# Power_Distribution_-_Spare_Load_Switch.net
KiCad netlist of a schematic drawn in Altium Designer
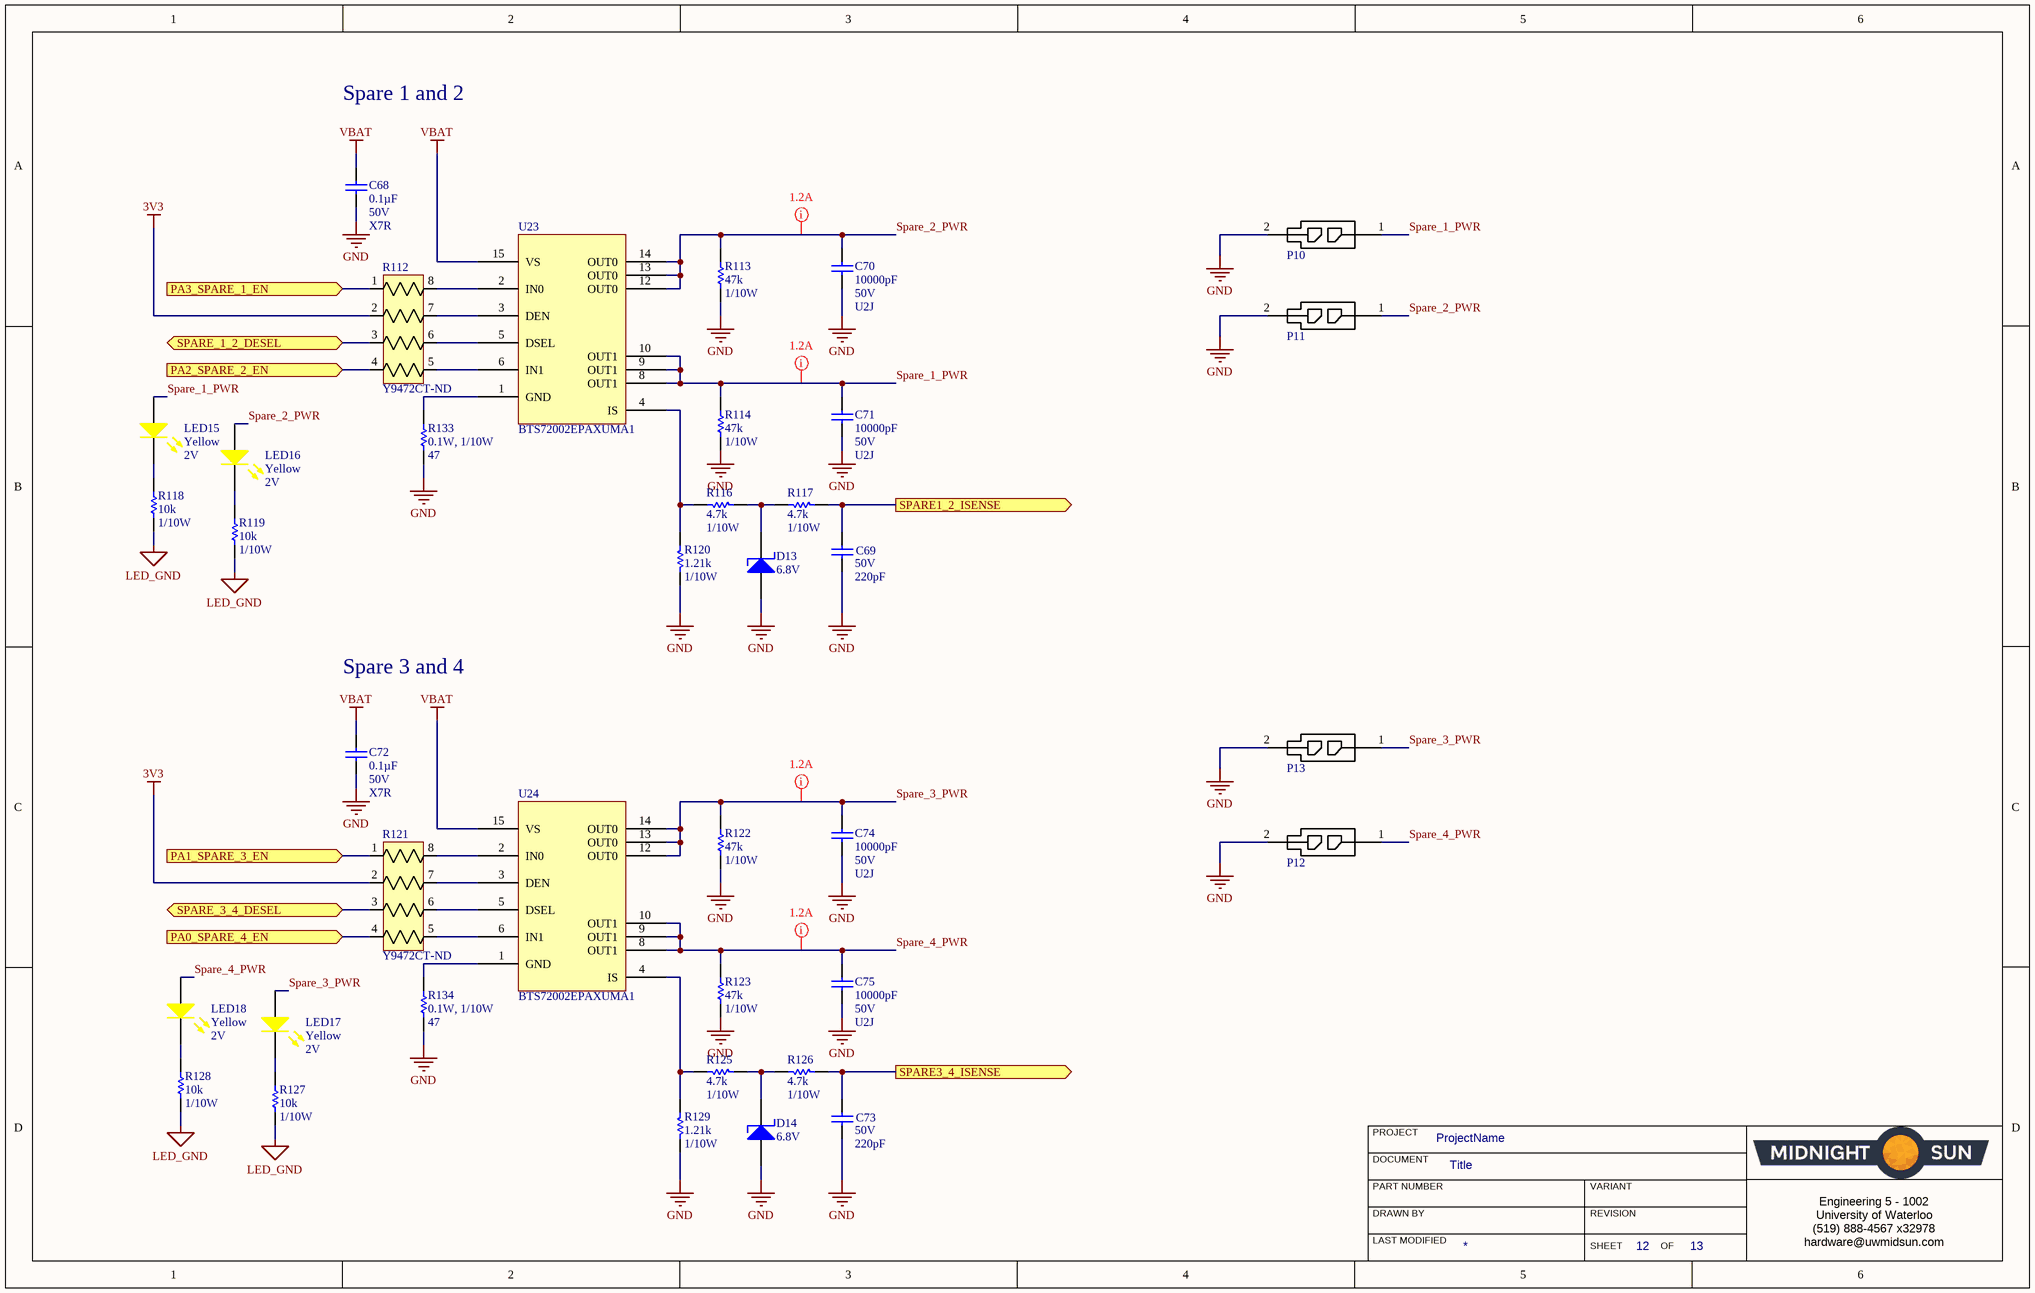
[diagram p0: Power Distribution - Spare Load Switch.SchDoc]

(export (version "E")
  (design (tool "Eeschema 10.0.6"))
  (components
    (comp (ref "C68")
      (value "CAP CER 0.1UF 50V 10% X7R 0603")
      (footprint "CAP, 0603")
      (description "0.10µF ±10% 50V Ceramic Capacitor X7R 0603 (1608 Metric)")
      (fields
        (field (name "TOLERANCE") "±10%")
        (field (name "CAPACITANCE") "0.1µF")
        (field (name "VOLTAGE") "50V")
        (field (name "TEMPERATURE COEFFICIENT") "X7R")
      )
      (libsource (lib "Schematic Diagrams") (part "CAP CER 0.1UF 50V 10% X7R 0603"))
    )
    (comp (ref "C69")
      (value "CAP CER 220PF 50V C0G/NP0 0603")
      (footprint "CAP, 0603")
      (description "220pF ±5% 50V Ceramic Capacitor C0G, NP0 0603 (1608 Metric)")
      (fields
        (field (name "MANUFACTURER") "KEMET")
        (field (name "TOLERANCE") "5%")
        (field (name "VOLTAGE RATING") "50V")
        (field (name "CAPACITANCE") "220pF")
      )
      (libsource (lib "Schematic Diagrams") (part "CAP CER 220PF 50V C0G/NP0 0603"))
    )
    (comp (ref "C70")
      (value "CAP CER 10nF 50V 5% X7R 0603")
      (footprint "CAP, 0603")
      (description "10000pF ±5% 50V Ceramic Capacitor U2J 0603 (1608 Metric)")
      (fields
        (field (name "TOLERANCE") "±5%")
        (field (name "CAPACITANCE") "10000pF")
        (field (name "VOLTAGE") "50V")
        (field (name "TEMPERATURE COEFFICIENT") "U2J")
      )
      (libsource (lib "Schematic Diagrams") (part "CAP CER 10nF 50V 5% X7R 0603"))
    )
    (comp (ref "C71")
      (value "CAP CER 10nF 50V 5% X7R 0603")
      (footprint "CAP, 0603")
      (description "10000pF ±5% 50V Ceramic Capacitor U2J 0603 (1608 Metric)")
      (fields
        (field (name "TOLERANCE") "±5%")
        (field (name "CAPACITANCE") "10000pF")
        (field (name "VOLTAGE") "50V")
        (field (name "TEMPERATURE COEFFICIENT") "U2J")
      )
      (libsource (lib "Schematic Diagrams") (part "CAP CER 10nF 50V 5% X7R 0603"))
    )
    (comp (ref "C72")
      (value "CAP CER 0.1UF 50V 10% X7R 0603")
      (footprint "CAP, 0603")
      (description "0.10µF ±10% 50V Ceramic Capacitor X7R 0603 (1608 Metric)")
      (fields
        (field (name "TOLERANCE") "±10%")
        (field (name "CAPACITANCE") "0.1µF")
        (field (name "VOLTAGE") "50V")
        (field (name "TEMPERATURE COEFFICIENT") "X7R")
      )
      (libsource (lib "Schematic Diagrams") (part "CAP CER 0.1UF 50V 10% X7R 0603"))
    )
    (comp (ref "C73")
      (value "CAP CER 220PF 50V C0G/NP0 0603")
      (footprint "CAP, 0603")
      (description "220pF ±5% 50V Ceramic Capacitor C0G, NP0 0603 (1608 Metric)")
      (fields
        (field (name "MANUFACTURER") "KEMET")
        (field (name "TOLERANCE") "5%")
        (field (name "VOLTAGE RATING") "50V")
        (field (name "CAPACITANCE") "220pF")
      )
      (libsource (lib "Schematic Diagrams") (part "CAP CER 220PF 50V C0G/NP0 0603"))
    )
    (comp (ref "C74")
      (value "CAP CER 10nF 50V 5% X7R 0603")
      (footprint "CAP, 0603")
      (description "10000pF ±5% 50V Ceramic Capacitor U2J 0603 (1608 Metric)")
      (fields
        (field (name "TOLERANCE") "±5%")
        (field (name "CAPACITANCE") "10000pF")
        (field (name "VOLTAGE") "50V")
        (field (name "TEMPERATURE COEFFICIENT") "U2J")
      )
      (libsource (lib "Schematic Diagrams") (part "CAP CER 10nF 50V 5% X7R 0603"))
    )
    (comp (ref "C75")
      (value "CAP CER 10nF 50V 5% X7R 0603")
      (footprint "CAP, 0603")
      (description "10000pF ±5% 50V Ceramic Capacitor U2J 0603 (1608 Metric)")
      (fields
        (field (name "TOLERANCE") "±5%")
        (field (name "CAPACITANCE") "10000pF")
        (field (name "VOLTAGE") "50V")
        (field (name "TEMPERATURE COEFFICIENT") "U2J")
      )
      (libsource (lib "Schematic Diagrams") (part "CAP CER 10nF 50V 5% X7R 0603"))
    )
    (comp (ref "D13")
      (value "6.8V")
      (footprint "DIODE SOD123")
      (description "Zener Diode 6.8V 500mW ±5% Surface Mount SOD-123")
      (fields (field (name "MANUFACTURER") "Diodes Incorporated") (field (name "TOLERANCE") "±5%"))
      (libsource (lib "Schematic Diagrams") (part "DIODE ZENER 6.8V 500MW SOD123"))
    )
    (comp (ref "D14")
      (value "6.8V")
      (footprint "DIODE SOD123")
      (description "Zener Diode 6.8V 500mW ±5% Surface Mount SOD-123")
      (fields (field (name "MANUFACTURER") "Diodes Incorporated") (field (name "TOLERANCE") "±5%"))
      (libsource (lib "Schematic Diagrams") (part "DIODE ZENER 6.8V 500MW SOD123"))
    )
    (comp (ref "LED15")
      (value "LED YELLOW CLEAR 2.1V 0603")
      (footprint "LED_0603")
      (description "Yellow 590nm LED Indication - Discrete 2V 0603 (1608 Metric)")
      (fields
        (field (name "MANUFACTURER") "Wurth Electronics Inc.")
        (field (name "MANUFACTURER PART NUMBER") "150060YS75000")
        (field (name "COLOR") "Yellow")
        (field (name "VOLTAGE - FORWARD (VF) (TYP)") "2V")
      )
      (libsource (lib "Schematic Diagrams") (part "LED YELLOW CLEAR 2.1V 0603"))
    )
    (comp (ref "LED16")
      (value "LED YELLOW CLEAR 2.1V 0603")
      (footprint "LED_0603")
      (description "Yellow 590nm LED Indication - Discrete 2V 0603 (1608 Metric)")
      (fields
        (field (name "MANUFACTURER") "Wurth Electronics Inc.")
        (field (name "MANUFACTURER PART NUMBER") "150060YS75000")
        (field (name "COLOR") "Yellow")
        (field (name "VOLTAGE - FORWARD (VF) (TYP)") "2V")
      )
      (libsource (lib "Schematic Diagrams") (part "LED YELLOW CLEAR 2.1V 0603"))
    )
    (comp (ref "LED17")
      (value "LED YELLOW CLEAR 2.1V 0603")
      (footprint "LED_0603")
      (description "Yellow 590nm LED Indication - Discrete 2V 0603 (1608 Metric)")
      (fields
        (field (name "MANUFACTURER") "Wurth Electronics Inc.")
        (field (name "MANUFACTURER PART NUMBER") "150060YS75000")
        (field (name "COLOR") "Yellow")
        (field (name "VOLTAGE - FORWARD (VF) (TYP)") "2V")
      )
      (libsource (lib "Schematic Diagrams") (part "LED YELLOW CLEAR 2.1V 0603"))
    )
    (comp (ref "LED18")
      (value "LED YELLOW CLEAR 2.1V 0603")
      (footprint "LED_0603")
      (description "Yellow 590nm LED Indication - Discrete 2V 0603 (1608 Metric)")
      (fields
        (field (name "MANUFACTURER") "Wurth Electronics Inc.")
        (field (name "MANUFACTURER PART NUMBER") "150060YS75000")
        (field (name "COLOR") "Yellow")
        (field (name "VOLTAGE - FORWARD (VF) (TYP)") "2V")
      )
      (libsource (lib "Schematic Diagrams") (part "LED YELLOW CLEAR 2.1V 0603"))
    )
    (comp (ref "P10")
      (value "CONN 2POS MICRO-FIT 3mm")
      (footprint "CONN, 2POS MICRO-FIT")
      (description "Connector Header Through Hole 2 position")
      (fields (field (name "MANUFACTURER") "Molex") (field (name "MANUFACTURER PART NUMBER") "43045-0227"))
      (libsource (lib "Schematic Diagrams") (part "CONN 2POS MICRO-FIT 3mm"))
    )
    (comp (ref "P11")
      (value "CONN 2POS MICRO-FIT 3mm")
      (footprint "CONN, 2POS MICRO-FIT")
      (description "Connector Header Through Hole 2 position")
      (fields (field (name "MANUFACTURER") "Molex") (field (name "MANUFACTURER PART NUMBER") "43045-0227"))
      (libsource (lib "Schematic Diagrams") (part "CONN 2POS MICRO-FIT 3mm"))
    )
    (comp (ref "P12")
      (value "CONN 2POS MICRO-FIT 3mm")
      (footprint "CONN, 2POS MICRO-FIT")
      (description "Connector Header Through Hole 2 position")
      (fields (field (name "MANUFACTURER") "Molex") (field (name "MANUFACTURER PART NUMBER") "43045-0227"))
      (libsource (lib "Schematic Diagrams") (part "CONN 2POS MICRO-FIT 3mm"))
    )
    (comp (ref "P13")
      (value "CONN 2POS MICRO-FIT 3mm")
      (footprint "CONN, 2POS MICRO-FIT")
      (description "Connector Header Through Hole 2 position")
      (fields (field (name "MANUFACTURER") "Molex") (field (name "MANUFACTURER PART NUMBER") "43045-0227"))
      (libsource (lib "Schematic Diagrams") (part "CONN 2POS MICRO-FIT 3mm"))
    )
    (comp (ref "R112")
      (value "RES ARRAY 4 RES 4.7K OHM 1206")
      (footprint "RES ARRAY 4RES 1206")
      (fields (field (name "TOLERANCE") "±5%") (field (name "SUPPLIER PART NUMBER 1") "Y9472CT-ND"))
      (libsource (lib "Schematic Diagrams") (part "RES ARRAY 4 RES 4.7K OHM 1206"))
    )
    (comp (ref "R113")
      (value "RES 47K OHM 1% 1/10W 0603")
      (footprint "RES, 0603")
      (description "47 kOhms ±1% 0.1W, 1/10W Chip Resistor 0603 (1608 Metric) Automotive AEC-Q200 Thick Film")
      (fields
        (field (name "MANUFACTURER") "Panasonic")
        (field (name "MANUFACTURER PART NUMBER") "ERJ3EKF4702V")
        (field (name "RESISTANCE") "47k")
        (field (name "POWER RATING") "1/10W")
      )
      (libsource (lib "Schematic Diagrams") (part "RES 47K OHM 1% 1/10W 0603"))
    )
    (comp (ref "R114")
      (value "RES 47K OHM 1% 1/10W 0603")
      (footprint "RES, 0603")
      (description "47 kOhms ±1% 0.1W, 1/10W Chip Resistor 0603 (1608 Metric) Automotive AEC-Q200 Thick Film")
      (fields
        (field (name "MANUFACTURER") "Panasonic")
        (field (name "MANUFACTURER PART NUMBER") "ERJ3EKF4702V")
        (field (name "RESISTANCE") "47k")
        (field (name "POWER RATING") "1/10W")
      )
      (libsource (lib "Schematic Diagrams") (part "RES 47K OHM 1% 1/10W 0603"))
    )
    (comp (ref "R116")
      (value "RES 4.7K OHM 1% 1/10W 0603")
      (footprint "RES, 0603")
      (description "4.7k Ohm ±1% 0.1W, 1/10W Chip Resistor 0603 (1608 Metric) Moisture Resistant Thick Film")
      (fields
        (field (name "TOLERANCE") "±1%")
        (field (name "RESISTANCE (OHMS)") "4.7k")
        (field (name "POWER (WATTS)") "1/10W")
      )
      (libsource (lib "Schematic Diagrams") (part "RES 4.7K OHM 1% 1/10W 0603"))
    )
    (comp (ref "R117")
      (value "RES 4.7K OHM 1% 1/10W 0603")
      (footprint "RES, 0603")
      (description "4.7k Ohm ±1% 0.1W, 1/10W Chip Resistor 0603 (1608 Metric) Moisture Resistant Thick Film")
      (fields
        (field (name "TOLERANCE") "±1%")
        (field (name "RESISTANCE (OHMS)") "4.7k")
        (field (name "POWER (WATTS)") "1/10W")
      )
      (libsource (lib "Schematic Diagrams") (part "RES 4.7K OHM 1% 1/10W 0603"))
    )
    (comp (ref "R118")
      (value "RES 10K OHM 1% 1/10W 0603")
      (footprint "RES, 0603")
      (description "RES SMD 10K OHM 1% 1/10W 0603")
      (fields
        (field (name "TOLERANCE") "±1%")
        (field (name "RESISTANCE") "10k")
        (field (name "POWER") "1/10W")
      )
      (libsource (lib "Schematic Diagrams") (part "RES 10K OHM 1% 1/10W 0603"))
    )
    (comp (ref "R119")
      (value "RES 10K OHM 1% 1/10W 0603")
      (footprint "RES, 0603")
      (description "RES SMD 10K OHM 1% 1/10W 0603")
      (fields
        (field (name "TOLERANCE") "±1%")
        (field (name "RESISTANCE") "10k")
        (field (name "POWER") "1/10W")
      )
      (libsource (lib "Schematic Diagrams") (part "RES 10K OHM 1% 1/10W 0603"))
    )
    (comp (ref "R120")
      (value "RES 1.21K OHM 1% 1/10W 0603")
      (footprint "RES, 0603")
      (description "1.21k Ohm ±1% 0.1W, 1/10W Chip Resistor 0603 (1608 Metric) Moisture Resistant Thick Film")
      (fields
        (field (name "TOLERANCE") "±1%")
        (field (name "RESISTANCE") "1.21k")
        (field (name "POWER") "1/10W")
      )
      (libsource (lib "Schematic Diagrams") (part "RES 1.21K OHM 1% 1/10W 0603"))
    )
    (comp (ref "R121")
      (value "RES ARRAY 4 RES 4.7K OHM 1206")
      (footprint "RES ARRAY 4RES 1206")
      (fields (field (name "TOLERANCE") "±5%") (field (name "SUPPLIER PART NUMBER 1") "Y9472CT-ND"))
      (libsource (lib "Schematic Diagrams") (part "RES ARRAY 4 RES 4.7K OHM 1206"))
    )
    (comp (ref "R122")
      (value "RES 47K OHM 1% 1/10W 0603")
      (footprint "RES, 0603")
      (description "47 kOhms ±1% 0.1W, 1/10W Chip Resistor 0603 (1608 Metric) Automotive AEC-Q200 Thick Film")
      (fields
        (field (name "MANUFACTURER") "Panasonic")
        (field (name "MANUFACTURER PART NUMBER") "ERJ3EKF4702V")
        (field (name "RESISTANCE") "47k")
        (field (name "POWER RATING") "1/10W")
      )
      (libsource (lib "Schematic Diagrams") (part "RES 47K OHM 1% 1/10W 0603"))
    )
    (comp (ref "R123")
      (value "RES 47K OHM 1% 1/10W 0603")
      (footprint "RES, 0603")
      (description "47 kOhms ±1% 0.1W, 1/10W Chip Resistor 0603 (1608 Metric) Automotive AEC-Q200 Thick Film")
      (fields
        (field (name "MANUFACTURER") "Panasonic")
        (field (name "MANUFACTURER PART NUMBER") "ERJ3EKF4702V")
        (field (name "RESISTANCE") "47k")
        (field (name "POWER RATING") "1/10W")
      )
      (libsource (lib "Schematic Diagrams") (part "RES 47K OHM 1% 1/10W 0603"))
    )
    (comp (ref "R125")
      (value "RES 4.7K OHM 1% 1/10W 0603")
      (footprint "RES, 0603")
      (description "4.7k Ohm ±1% 0.1W, 1/10W Chip Resistor 0603 (1608 Metric) Moisture Resistant Thick Film")
      (fields
        (field (name "TOLERANCE") "±1%")
        (field (name "RESISTANCE (OHMS)") "4.7k")
        (field (name "POWER (WATTS)") "1/10W")
      )
      (libsource (lib "Schematic Diagrams") (part "RES 4.7K OHM 1% 1/10W 0603"))
    )
    (comp (ref "R126")
      (value "RES 4.7K OHM 1% 1/10W 0603")
      (footprint "RES, 0603")
      (description "4.7k Ohm ±1% 0.1W, 1/10W Chip Resistor 0603 (1608 Metric) Moisture Resistant Thick Film")
      (fields
        (field (name "TOLERANCE") "±1%")
        (field (name "RESISTANCE (OHMS)") "4.7k")
        (field (name "POWER (WATTS)") "1/10W")
      )
      (libsource (lib "Schematic Diagrams") (part "RES 4.7K OHM 1% 1/10W 0603"))
    )
    (comp (ref "R127")
      (value "RES 10K OHM 1% 1/10W 0603")
      (footprint "RES, 0603")
      (description "RES SMD 10K OHM 1% 1/10W 0603")
      (fields
        (field (name "TOLERANCE") "±1%")
        (field (name "RESISTANCE") "10k")
        (field (name "POWER") "1/10W")
      )
      (libsource (lib "Schematic Diagrams") (part "RES 10K OHM 1% 1/10W 0603"))
    )
    (comp (ref "R128")
      (value "RES 10K OHM 1% 1/10W 0603")
      (footprint "RES, 0603")
      (description "RES SMD 10K OHM 1% 1/10W 0603")
      (fields
        (field (name "TOLERANCE") "±1%")
        (field (name "RESISTANCE") "10k")
        (field (name "POWER") "1/10W")
      )
      (libsource (lib "Schematic Diagrams") (part "RES 10K OHM 1% 1/10W 0603"))
    )
    (comp (ref "R129")
      (value "RES 1.21K OHM 1% 1/10W 0603")
      (footprint "RES, 0603")
      (description "1.21k Ohm ±1% 0.1W, 1/10W Chip Resistor 0603 (1608 Metric) Moisture Resistant Thick Film")
      (fields
        (field (name "TOLERANCE") "±1%")
        (field (name "RESISTANCE") "1.21k")
        (field (name "POWER") "1/10W")
      )
      (libsource (lib "Schematic Diagrams") (part "RES 1.21K OHM 1% 1/10W 0603"))
    )
    (comp (ref "R133")
      (value "RES SMD 47 OHM 1% 1/10W 0603")
      (footprint "RES, 0603")
      (fields
        (field (name "TOLERANCE") "±1%")
        (field (name "POWER (WATTS)") "0.1W, 1/10W")
        (field (name "VALUES") "47")
      )
      (libsource (lib "Schematic Diagrams") (part "RES SMD 47 OHM 1% 1/10W 0603"))
    )
    (comp (ref "R134")
      (value "RES SMD 47 OHM 1% 1/10W 0603")
      (footprint "RES, 0603")
      (fields
        (field (name "TOLERANCE") "±1%")
        (field (name "POWER (WATTS)") "0.1W, 1/10W")
        (field (name "VALUES") "47")
      )
      (libsource (lib "Schematic Diagrams") (part "RES SMD 47 OHM 1% 1/10W 0603"))
    )
    (comp (ref "U23")
      (value "IC LOAD SWITCH BTS7200-2EPA PG-TSDSO-14_1")
      (footprint "IC LOAD SWITCH PG-TSDSO-14-22")
      (description "Power Switch/Driver 1:1 N-Channel 1.2A PG-TSDSO-14-22")
      (fields
        (field (name "MANUFACTURER") "Infineon")
        (field (name "MANUFACTURER PART NUMBER") "BTS72002EPAXUMA1")
      )
      (libsource (lib "Schematic Diagrams") (part "IC LOAD SWITCH BTS7200-2EPA PG-TSDSO-14_1"))
    )
    (comp (ref "U24")
      (value "IC LOAD SWITCH BTS7200-2EPA PG-TSDSO-14_1")
      (footprint "IC LOAD SWITCH PG-TSDSO-14-22")
      (description "Power Switch/Driver 1:1 N-Channel 1.2A PG-TSDSO-14-22")
      (fields
        (field (name "MANUFACTURER") "Infineon")
        (field (name "MANUFACTURER PART NUMBER") "BTS72002EPAXUMA1")
      )
      (libsource (lib "Schematic Diagrams") (part "IC LOAD SWITCH BTS7200-2EPA PG-TSDSO-14_1"))
    )
  )
  (nets
    (net (code "1") (name "/PA0_SPARE_4_EN") (class "Default")
      (node (ref "R121") (pin "4") (pinfunction "4_4") (pintype "passive"))
    )
    (net (code "2") (name "/PA1_SPARE_3_EN") (class "Default")
      (node (ref "R121") (pin "1") (pinfunction "1_1") (pintype "passive"))
    )
    (net (code "3") (name "/PA2_SPARE_2_EN") (class "Default")
      (node (ref "R112") (pin "4") (pinfunction "4_4") (pintype "passive"))
    )
    (net (code "4") (name "/PA3_SPARE_1_EN") (class "Default")
      (node (ref "R112") (pin "1") (pinfunction "1_1") (pintype "passive"))
    )
    (net (code "5") (name "/SPARE1_2_ISENSE") (class "Default")
      (node (ref "C69") (pin "1") (pinfunction "1_1") (pintype "passive"))
      (node (ref "R117") (pin "1") (pinfunction "1_1") (pintype "passive"))
    )
    (net (code "6") (name "/SPARE3_4_ISENSE") (class "Default")
      (node (ref "C73") (pin "1") (pinfunction "1_1") (pintype "passive"))
      (node (ref "R126") (pin "1") (pinfunction "1_1") (pintype "passive"))
    )
    (net (code "7") (name "/SPARE_1_2_DESEL") (class "Default")
      (node (ref "R112") (pin "3") (pinfunction "3_3") (pintype "passive"))
    )
    (net (code "8") (name "/SPARE_3_4_DESEL") (class "Default")
      (node (ref "R121") (pin "3") (pinfunction "3_3") (pintype "passive"))
    )
    (net (code "9") (name "/Spare_1_PWR") (class "Default")
      (node (ref "C71") (pin "1") (pinfunction "1_1") (pintype "passive"))
      (node (ref "LED15") (pin "1") (pinfunction "A_1") (pintype "passive"))
      (node (ref "P10") (pin "1") (pinfunction "1_1") (pintype "passive"))
      (node (ref "R114") (pin "1") (pinfunction "1_1") (pintype "passive"))
      (node (ref "U23") (pin "10") (pinfunction "OUT1_10") (pintype "passive"))
      (node (ref "U23") (pin "8") (pinfunction "OUT1_8") (pintype "passive"))
      (node (ref "U23") (pin "9") (pinfunction "OUT1_9") (pintype "passive"))
    )
    (net (code "10") (name "/Spare_2_PWR") (class "Default")
      (node (ref "C70") (pin "1") (pinfunction "1_1") (pintype "passive"))
      (node (ref "LED16") (pin "1") (pinfunction "A_1") (pintype "passive"))
      (node (ref "P11") (pin "1") (pinfunction "1_1") (pintype "passive"))
      (node (ref "R113") (pin "1") (pinfunction "1_1") (pintype "passive"))
      (node (ref "U23") (pin "12") (pinfunction "OUT0_12") (pintype "passive"))
      (node (ref "U23") (pin "13") (pinfunction "OUT0_13") (pintype "passive"))
      (node (ref "U23") (pin "14") (pinfunction "OUT0_14") (pintype "passive"))
    )
    (net (code "11") (name "/Spare_3_PWR") (class "Default")
      (node (ref "C74") (pin "1") (pinfunction "1_1") (pintype "passive"))
      (node (ref "LED17") (pin "1") (pinfunction "A_1") (pintype "passive"))
      (node (ref "P13") (pin "1") (pinfunction "1_1") (pintype "passive"))
      (node (ref "R122") (pin "1") (pinfunction "1_1") (pintype "passive"))
      (node (ref "U24") (pin "12") (pinfunction "OUT0_12") (pintype "passive"))
      (node (ref "U24") (pin "13") (pinfunction "OUT0_13") (pintype "passive"))
      (node (ref "U24") (pin "14") (pinfunction "OUT0_14") (pintype "passive"))
    )
    (net (code "12") (name "/Spare_4_PWR") (class "Default")
      (node (ref "C75") (pin "1") (pinfunction "1_1") (pintype "passive"))
      (node (ref "LED18") (pin "1") (pinfunction "A_1") (pintype "passive"))
      (node (ref "P12") (pin "1") (pinfunction "1_1") (pintype "passive"))
      (node (ref "R123") (pin "1") (pinfunction "1_1") (pintype "passive"))
      (node (ref "U24") (pin "10") (pinfunction "OUT1_10") (pintype "passive"))
      (node (ref "U24") (pin "8") (pinfunction "OUT1_8") (pintype "passive"))
      (node (ref "U24") (pin "9") (pinfunction "OUT1_9") (pintype "passive"))
    )
    (net (code "13") (name "3V3") (class "Default")
      (node (ref "R112") (pin "2") (pinfunction "2_2") (pintype "passive"))
      (node (ref "R121") (pin "2") (pinfunction "2_2") (pintype "passive"))
    )
    (net (code "14") (name "GND") (class "Default")
      (node (ref "C68") (pin "2") (pinfunction "2_2") (pintype "passive"))
      (node (ref "C69") (pin "2") (pinfunction "2_2") (pintype "passive"))
      (node (ref "C70") (pin "2") (pinfunction "2_2") (pintype "passive"))
      (node (ref "C71") (pin "2") (pinfunction "2_2") (pintype "passive"))
      (node (ref "C72") (pin "2") (pinfunction "2_2") (pintype "passive"))
      (node (ref "C73") (pin "2") (pinfunction "2_2") (pintype "passive"))
      (node (ref "C74") (pin "2") (pinfunction "2_2") (pintype "passive"))
      (node (ref "C75") (pin "2") (pinfunction "2_2") (pintype "passive"))
      (node (ref "D13") (pin "2") (pinfunction "A_2") (pintype "passive"))
      (node (ref "D14") (pin "2") (pinfunction "A_2") (pintype "passive"))
      (node (ref "P10") (pin "2") (pinfunction "2_2") (pintype "passive"))
      (node (ref "P11") (pin "2") (pinfunction "2_2") (pintype "passive"))
      (node (ref "P12") (pin "2") (pinfunction "2_2") (pintype "passive"))
      (node (ref "P13") (pin "2") (pinfunction "2_2") (pintype "passive"))
      (node (ref "R113") (pin "2") (pinfunction "2_2") (pintype "passive"))
      (node (ref "R114") (pin "2") (pinfunction "2_2") (pintype "passive"))
      (node (ref "R120") (pin "2") (pinfunction "2_2") (pintype "passive"))
      (node (ref "R122") (pin "2") (pinfunction "2_2") (pintype "passive"))
      (node (ref "R123") (pin "2") (pinfunction "2_2") (pintype "passive"))
      (node (ref "R129") (pin "2") (pinfunction "2_2") (pintype "passive"))
      (node (ref "R133") (pin "2") (pinfunction "2_2") (pintype "passive"))
      (node (ref "R134") (pin "2") (pinfunction "2_2") (pintype "passive"))
    )
    (net (code "15") (name "LED_GND") (class "Default")
      (node (ref "R118") (pin "2") (pinfunction "2_2") (pintype "passive"))
      (node (ref "R119") (pin "2") (pinfunction "2_2") (pintype "passive"))
      (node (ref "R127") (pin "2") (pinfunction "2_2") (pintype "passive"))
      (node (ref "R128") (pin "2") (pinfunction "2_2") (pintype "passive"))
    )
    (net (code "16") (name "Net-(D13-K)") (class "Default")
      (node (ref "D13") (pin "1") (pinfunction "K_1") (pintype "passive"))
      (node (ref "R116") (pin "1") (pinfunction "1_1") (pintype "passive"))
      (node (ref "R117") (pin "2") (pinfunction "2_2") (pintype "passive"))
    )
    (net (code "17") (name "Net-(D14-K)") (class "Default")
      (node (ref "D14") (pin "1") (pinfunction "K_1") (pintype "passive"))
      (node (ref "R125") (pin "1") (pinfunction "1_1") (pintype "passive"))
      (node (ref "R126") (pin "2") (pinfunction "2_2") (pintype "passive"))
    )
    (net (code "18") (name "Net-(LED15-K)") (class "Default")
      (node (ref "LED15") (pin "2") (pinfunction "K_2") (pintype "passive"))
      (node (ref "R118") (pin "1") (pinfunction "1_1") (pintype "passive"))
    )
    (net (code "19") (name "Net-(LED16-K)") (class "Default")
      (node (ref "LED16") (pin "2") (pinfunction "K_2") (pintype "passive"))
      (node (ref "R119") (pin "1") (pinfunction "1_1") (pintype "passive"))
    )
    (net (code "20") (name "Net-(LED17-K)") (class "Default")
      (node (ref "LED17") (pin "2") (pinfunction "K_2") (pintype "passive"))
      (node (ref "R127") (pin "1") (pinfunction "1_1") (pintype "passive"))
    )
    (net (code "21") (name "Net-(LED18-K)") (class "Default")
      (node (ref "LED18") (pin "2") (pinfunction "K_2") (pintype "passive"))
      (node (ref "R128") (pin "1") (pinfunction "1_1") (pintype "passive"))
    )
    (net (code "22") (name "Net-(U23-DEN)") (class "Default")
      (node (ref "R112") (pin "7") (pinfunction "7_7") (pintype "passive"))
      (node (ref "U23") (pin "3") (pinfunction "DEN_3") (pintype "passive"))
    )
    (net (code "23") (name "Net-(U23-DSEL)") (class "Default")
      (node (ref "R112") (pin "6") (pinfunction "6_6") (pintype "passive"))
      (node (ref "U23") (pin "5") (pinfunction "DSEL_5") (pintype "passive"))
    )
    (net (code "24") (name "Net-(U23-GND)") (class "Default")
      (node (ref "R133") (pin "1") (pinfunction "1_1") (pintype "passive"))
      (node (ref "U23") (pin "1") (pinfunction "GND_1") (pintype "passive"))
    )
    (net (code "25") (name "Net-(U23-IN0)") (class "Default")
      (node (ref "R112") (pin "8") (pinfunction "8_8") (pintype "passive"))
      (node (ref "U23") (pin "2") (pinfunction "IN0_2") (pintype "passive"))
    )
    (net (code "26") (name "Net-(U23-IN1)") (class "Default")
      (node (ref "R112") (pin "5") (pinfunction "5_5") (pintype "passive"))
      (node (ref "U23") (pin "6") (pinfunction "IN1_6") (pintype "passive"))
    )
    (net (code "27") (name "Net-(U23-IS)") (class "Default")
      (node (ref "R116") (pin "2") (pinfunction "2_2") (pintype "passive"))
      (node (ref "R120") (pin "1") (pinfunction "1_1") (pintype "passive"))
      (node (ref "U23") (pin "4") (pinfunction "IS_4") (pintype "passive"))
    )
    (net (code "28") (name "Net-(U24-DEN)") (class "Default")
      (node (ref "R121") (pin "7") (pinfunction "7_7") (pintype "passive"))
      (node (ref "U24") (pin "3") (pinfunction "DEN_3") (pintype "passive"))
    )
    (net (code "29") (name "Net-(U24-DSEL)") (class "Default")
      (node (ref "R121") (pin "6") (pinfunction "6_6") (pintype "passive"))
      (node (ref "U24") (pin "5") (pinfunction "DSEL_5") (pintype "passive"))
    )
    (net (code "30") (name "Net-(U24-GND)") (class "Default")
      (node (ref "R134") (pin "1") (pinfunction "1_1") (pintype "passive"))
      (node (ref "U24") (pin "1") (pinfunction "GND_1") (pintype "passive"))
    )
    (net (code "31") (name "Net-(U24-IN0)") (class "Default")
      (node (ref "R121") (pin "8") (pinfunction "8_8") (pintype "passive"))
      (node (ref "U24") (pin "2") (pinfunction "IN0_2") (pintype "passive"))
    )
    (net (code "32") (name "Net-(U24-IN1)") (class "Default")
      (node (ref "R121") (pin "5") (pinfunction "5_5") (pintype "passive"))
      (node (ref "U24") (pin "6") (pinfunction "IN1_6") (pintype "passive"))
    )
    (net (code "33") (name "Net-(U24-IS)") (class "Default")
      (node (ref "R125") (pin "2") (pinfunction "2_2") (pintype "passive"))
      (node (ref "R129") (pin "1") (pinfunction "1_1") (pintype "passive"))
      (node (ref "U24") (pin "4") (pinfunction "IS_4") (pintype "passive"))
    )
    (net (code "34") (name "VBAT") (class "Default")
      (node (ref "C68") (pin "1") (pinfunction "1_1") (pintype "passive"))
      (node (ref "C72") (pin "1") (pinfunction "1_1") (pintype "passive"))
      (node (ref "U23") (pin "15") (pinfunction "VS_15") (pintype "passive"))
      (node (ref "U24") (pin "15") (pinfunction "VS_15") (pintype "passive"))
    )
  )
)
